# Expansion_board.net
KiCad netlist of a schematic drawn in Altium Designer
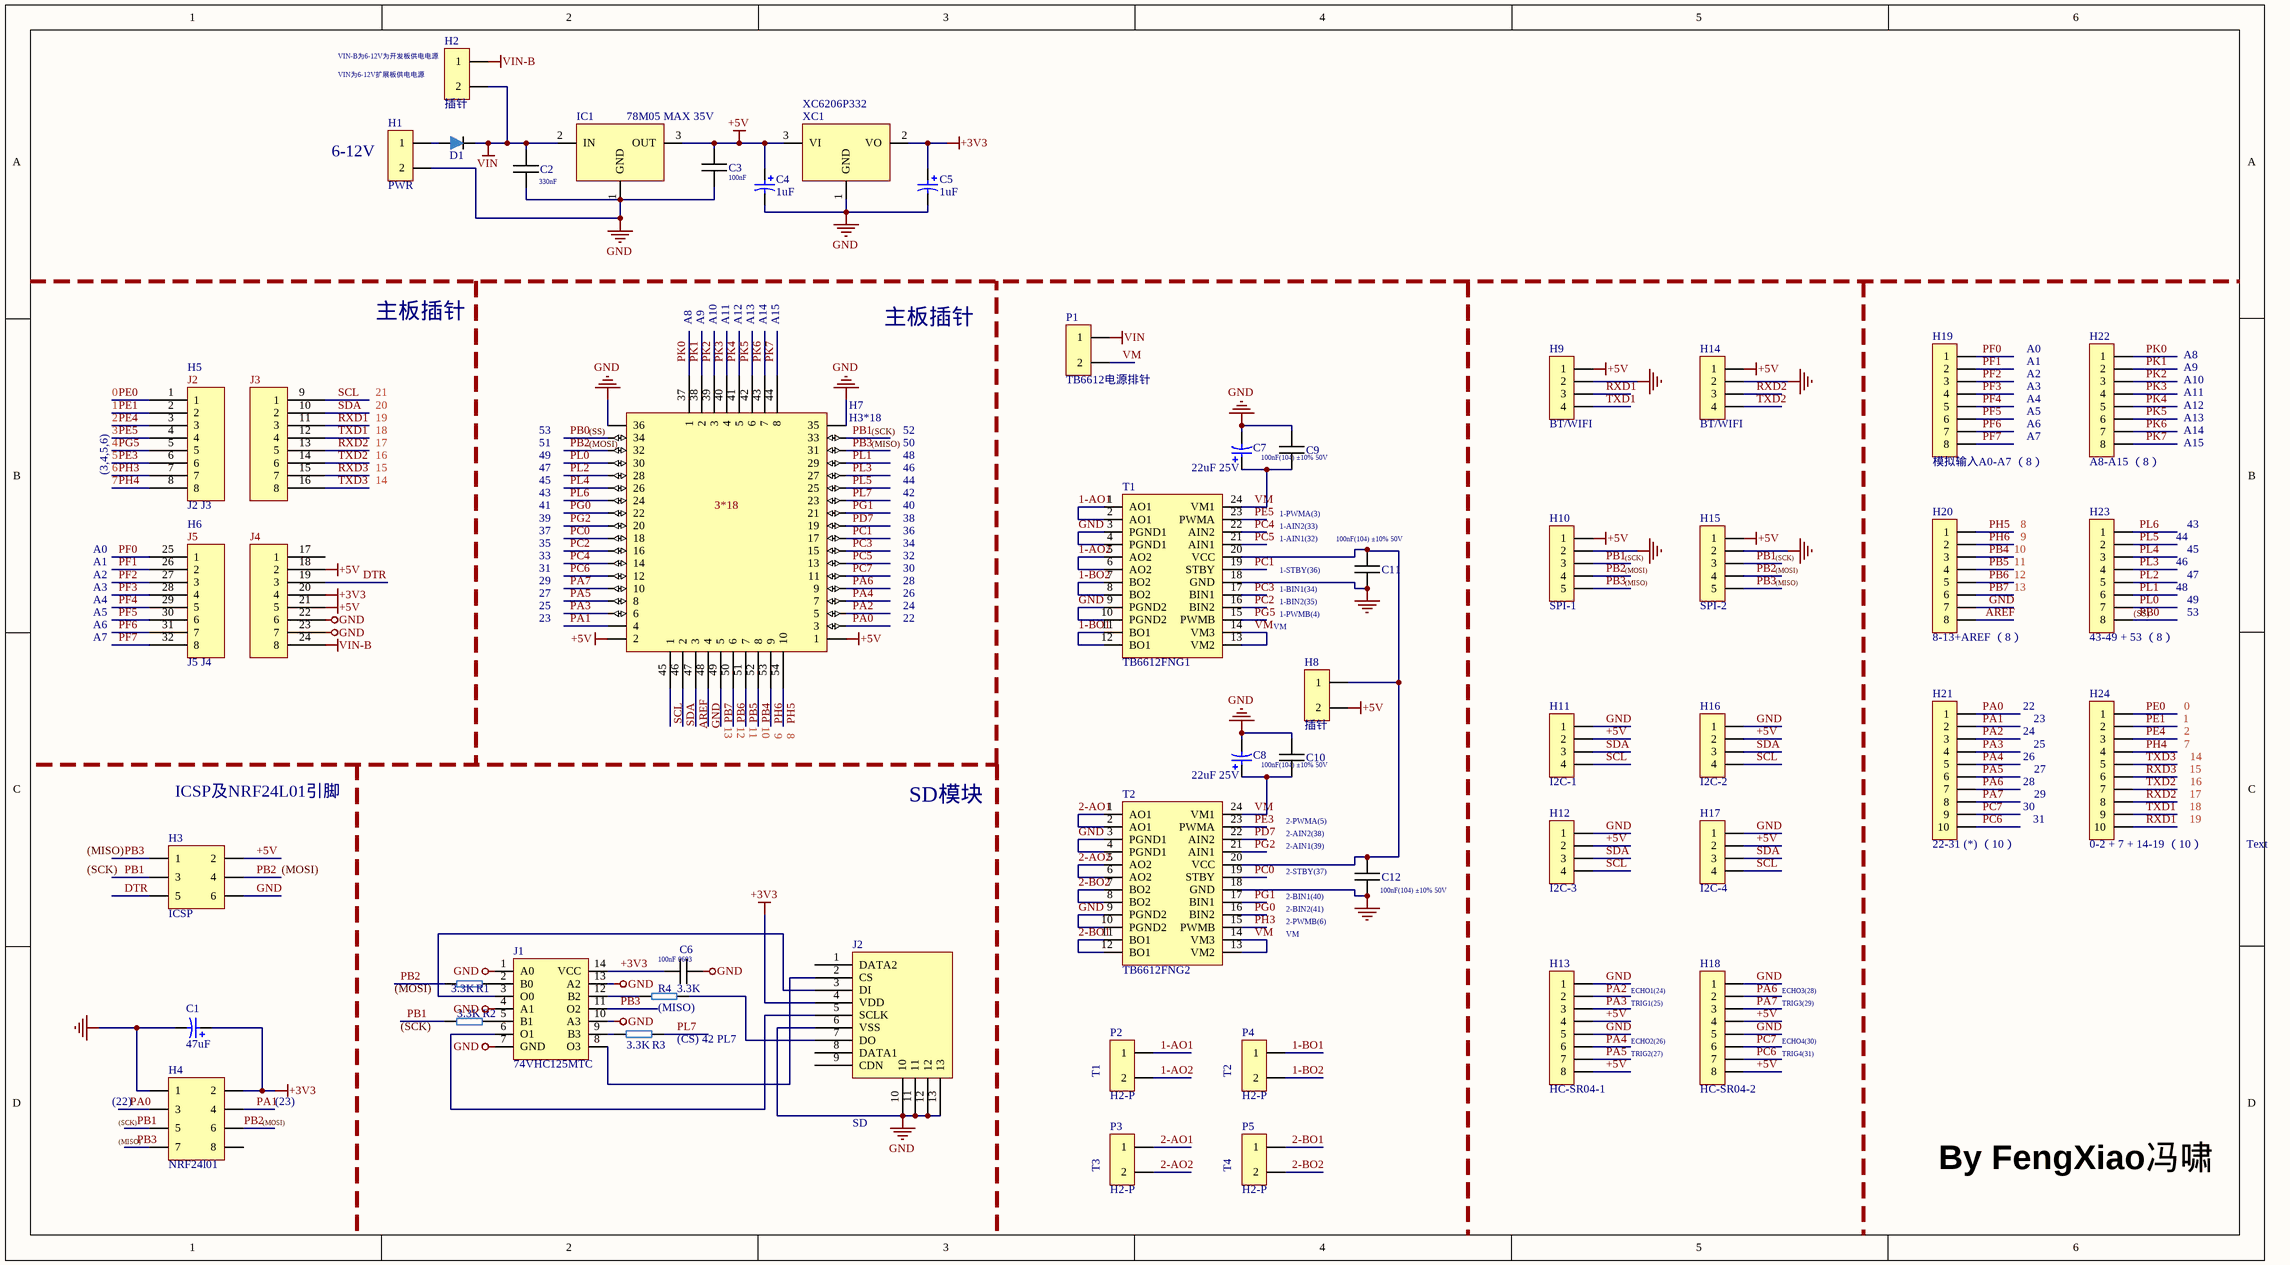
[diagram p0: Expansion board.SchDoc]

(export (version "E")
  (design (tool "Eeschema 10.0.6"))
  (components
    (comp (ref "C1")
      (value "47uF")
      (footprint "极性电容")
      (description "极性电容器")
      (fields (field (name "PUBLISHER") "Altium Limited"))
      (libsource (lib "Mega2560原理图库") (part "Cap Pol极性电容"))
    )
    (comp (ref "C2") (value "330nF") (footprint "0805") (libsource (lib "Expansion board") (part "CAP-N")))
    (comp (ref "C3") (value "100nF") (footprint "0805") (libsource (lib "Expansion board") (part "CAP-N")))
    (comp (ref "C4")
      (value "1uF")
      (footprint "0603")
      (description "极性电容器")
      (fields (field (name "PUBLISHER") "Altium Limited"))
      (libsource (lib "Expansion board") (part "Cap"))
    )
    (comp (ref "C5")
      (value "1uF")
      (footprint "0603")
      (description "极性电容器")
      (fields (field (name "PUBLISHER") "Altium Limited"))
      (libsource (lib "Expansion board") (part "Cap"))
    )
    (comp (ref "C6")
      (value "100nF 0603")
      (footprint "0603")
      (libsource (lib "Expansion board") (part "CAP-N"))
    )
    (comp (ref "C7")
      (value "22uF 25V")
      (footprint "极性电容")
      (description "极性电容器")
      (fields (field (name "PUBLISHER") "Altium Limited"))
      (libsource (lib "Mega2560原理图库") (part "Cap Pol极性电容"))
    )
    (comp (ref "C8")
      (value "22uF 25V")
      (footprint "极性电容")
      (description "极性电容器")
      (fields (field (name "PUBLISHER") "Altium Limited"))
      (libsource (lib "Mega2560原理图库") (part "Cap Pol极性电容"))
    )
    (comp (ref "C9")
      (value "100nF(104) ±10% 50V")
      (footprint "0805")
      (libsource (lib "Mega2560原理图库") (part "CAP-0805"))
    )
    (comp (ref "C10")
      (value "100nF(104) ±10% 50V")
      (footprint "0805")
      (libsource (lib "Mega2560原理图库") (part "CAP-0805"))
    )
    (comp (ref "C11")
      (value "100nF(104) ±10% 50V")
      (footprint "0805")
      (libsource (lib "Expansion board") (part "CAP-0805"))
    )
    (comp (ref "C12")
      (value "100nF(104) ±10% 50V")
      (footprint "0805")
      (libsource (lib "Mega2560原理图库") (part "CAP-0805"))
    )
    (comp (ref "D1") (value "二极管") (footprint "1206 +-") (libsource (lib "Expansion board") (part "二极管")))
    (comp (ref "H1") (value "PWR") (footprint "插线端子2P") (libsource (lib "Expansion board") (part "H2")))
    (comp (ref "H2")
      (value "插针")
      (footprint "H2")
      (description "排针类")
      (libsource (lib "Expansion board") (part "H2"))
    )
    (comp (ref "H3") (value "ICSP") (footprint "H2*3") (libsource (lib "Expansion board") (part "H3*2")))
    (comp (ref "H4")
      (value "NRF24l01")
      (footprint "H2*4")
      (libsource (lib "Expansion board") (part "Header 2*4"))
    )
    (comp (ref "H5") (value "J2 J3") (footprint "J2J3") (libsource (lib "Expansion board") (part "J2-3")))
    (comp (ref "H6") (value "J5 J4") (footprint "J5J4") (libsource (lib "Expansion board") (part "J5-4")))
    (comp (ref "H7") (value "H3*18") (footprint "H3*18") (libsource (lib "Expansion board") (part "H3*18")))
    (comp (ref "H8")
      (value "插针")
      (footprint "H2")
      (description "排针类")
      (libsource (lib "Expansion board") (part "H2"))
    )
    (comp (ref "H9") (value "BT/WIFI") (footprint "H4") (libsource (lib "Expansion board") (part "H4")))
    (comp (ref "H10") (value "SPI-1") (footprint "H5") (libsource (lib "Expansion board") (part "H5")))
    (comp (ref "H11") (value "I2C-1") (footprint "H4") (libsource (lib "Expansion board") (part "H4")))
    (comp (ref "H12") (value "I2C-3") (footprint "H4") (libsource (lib "Expansion board") (part "H4")))
    (comp (ref "H13") (value "HC-SR04-1") (footprint "H8") (libsource (lib "Expansion board") (part "H8")))
    (comp (ref "H14") (value "BT/WIFI") (footprint "H4") (libsource (lib "Expansion board") (part "H4")))
    (comp (ref "H15") (value "SPI-2") (footprint "H5") (libsource (lib "Expansion board") (part "H5")))
    (comp (ref "H16") (value "I2C-2") (footprint "H4") (libsource (lib "Expansion board") (part "H4")))
    (comp (ref "H17") (value "I2C-4") (footprint "H4") (libsource (lib "Expansion board") (part "H4")))
    (comp (ref "H18") (value "HC-SR04-2") (footprint "H8") (libsource (lib "Expansion board") (part "H8")))
    (comp (ref "H19")
      (value "模拟输入A0-A7 （8）")
      (footprint "H8")
      (libsource (lib "Expansion board") (part "H8"))
    )
    (comp (ref "H20")
      (value "8-13+AREF （8）")
      (footprint "H8")
      (libsource (lib "Expansion board") (part "H8"))
    )
    (comp (ref "H21")
      (value "22-31 (*) （10）")
      (footprint "H10")
      (libsource (lib "Expansion board") (part "H10"))
    )
    (comp (ref "H22") (value "A8-A15 （8）") (footprint "H8") (libsource (lib "Expansion board") (part "H8")))
    (comp (ref "H23")
      (value "43-49 + 53 （8）")
      (footprint "H8")
      (libsource (lib "Expansion board") (part "H8"))
    )
    (comp (ref "H24")
      (value "0-2 + 7 + 14-19 （10）")
      (footprint "H10")
      (libsource (lib "Expansion board") (part "H10"))
    )
    (comp (ref "IC1")
      (value "78M05 MAX 35V")
      (footprint "78M05")
      (description "MAX 18V")
      (libsource (lib "Expansion board") (part "78M05-5.0V"))
    )
    (comp (ref "J1")
      (value "74VHC125MTC")
      (footprint "74VHC125MTC")
      (libsource (lib "Expansion board") (part "74VHC125MCT"))
    )
    (comp (ref "J2") (value "SD") (footprint "SD") (libsource (lib "Expansion board") (part "SD")))
    (comp (ref "P1")
      (value "TB6612电源排针")
      (footprint "H2")
      (description "排管类")
      (libsource (lib "Expansion board") (part "H2-P"))
    )
    (comp (ref "P2")
      (value "H2-P")
      (footprint "插线端子2P")
      (description "排管类")
      (libsource (lib "Expansion board") (part "H2-P"))
    )
    (comp (ref "P3")
      (value "H2-P")
      (footprint "插线端子2P")
      (description "排管类")
      (libsource (lib "Expansion board") (part "H2-P"))
    )
    (comp (ref "P4")
      (value "H2-P")
      (footprint "插线端子2P")
      (description "排管类")
      (libsource (lib "Expansion board") (part "H2-P"))
    )
    (comp (ref "P5")
      (value "H2-P")
      (footprint "插线端子2P")
      (description "排管类")
      (libsource (lib "Expansion board") (part "H2-P"))
    )
    (comp (ref "R1") (value "3.3K") (footprint "0805") (libsource (lib "Expansion board") (part "RES")))
    (comp (ref "R2") (value "3.3K") (footprint "0805") (libsource (lib "Expansion board") (part "RES")))
    (comp (ref "R3") (value "3.3K") (footprint "0805") (libsource (lib "Expansion board") (part "RES")))
    (comp (ref "R4") (value "3.3K") (footprint "0805") (libsource (lib "Expansion board") (part "RES")))
    (comp (ref "T1")
      (value "TB6612FNG1")
      (footprint "TB6612GNG")
      (libsource (lib "Expansion board") (part "TB6612"))
    )
    (comp (ref "T2")
      (value "TB6612FNG2")
      (footprint "TB6612GNG")
      (libsource (lib "Expansion board") (part "TB6612"))
    )
    (comp (ref "XC1")
      (value "XC6206P332")
      (footprint "XC6206P332-3.3v")
      (description "3.3V限性稳压器")
      (libsource (lib "Expansion board") (part "XC6206P332"))
    )
  )
  (nets
    (net (code "1") (name "+3V3") (class "Default")
      (node (ref "C1") (pin "1") (pinfunction "1_1") (pintype "passive"))
      (node (ref "C5") (pin "1") (pinfunction "1_1") (pintype "passive"))
      (node (ref "C6") (pin "1") (pinfunction "1_1") (pintype "passive"))
      (node (ref "H4") (pin "2") (pinfunction "2_2") (pintype "passive"))
      (node (ref "H6") (pin "20") (pinfunction "4_20") (pintype "passive"))
      (node (ref "J1") (pin "14") (pinfunction "VCC_14") (pintype "passive"))
      (node (ref "J2") (pin "4") (pinfunction "VDD_4") (pintype "passive"))
      (node (ref "XC1") (pin "2") (pinfunction "VO_2") (pintype "passive"))
    )
    (net (code "2") (name "+5V") (class "Default")
      (node (ref "C3") (pin "2") (pinfunction "2_2") (pintype "passive"))
      (node (ref "C4") (pin "1") (pinfunction "1_1") (pintype "passive"))
      (node (ref "H10") (pin "1") (pinfunction "1_1") (pintype "passive"))
      (node (ref "H11") (pin "2") (pinfunction "2_2") (pintype "passive"))
      (node (ref "H12") (pin "2") (pinfunction "2_2") (pintype "passive"))
      (node (ref "H13") (pin "4") (pinfunction "4_4") (pintype "passive"))
      (node (ref "H13") (pin "8") (pinfunction "8_8") (pintype "passive"))
      (node (ref "H14") (pin "1") (pinfunction "1_1") (pintype "passive"))
      (node (ref "H15") (pin "1") (pinfunction "1_1") (pintype "passive"))
      (node (ref "H16") (pin "2") (pinfunction "2_2") (pintype "passive"))
      (node (ref "H17") (pin "2") (pinfunction "2_2") (pintype "passive"))
      (node (ref "H18") (pin "4") (pinfunction "4_4") (pintype "passive"))
      (node (ref "H18") (pin "8") (pinfunction "8_8") (pintype "passive"))
      (node (ref "H3") (pin "2") (pinfunction "2_2") (pintype "passive"))
      (node (ref "H6") (pin "18") (pinfunction "2_18") (pintype "passive"))
      (node (ref "H6") (pin "21") (pinfunction "5_21") (pintype "passive"))
      (node (ref "H7") (pin "1") (pinfunction "1_1") (pintype "power_in"))
      (node (ref "H7") (pin "2") (pinfunction "2_2") (pintype "power_in"))
      (node (ref "H8") (pin "2") (pinfunction "2_2") (pintype "passive"))
      (node (ref "H9") (pin "1") (pinfunction "1_1") (pintype "passive"))
      (node (ref "IC1") (pin "3") (pinfunction "OUT_3") (pintype "passive"))
      (node (ref "XC1") (pin "3") (pinfunction "VI_3") (pintype "passive"))
    )
    (net (code "3") (name "/1-AO1") (class "Default")
      (node (ref "P2") (pin "1") (pinfunction "1_1") (pintype "passive"))
      (node (ref "T1") (pin "1") (pinfunction "AO1_1") (pintype "passive"))
      (node (ref "T1") (pin "2") (pinfunction "AO1_2") (pintype "passive"))
    )
    (net (code "4") (name "/1-AO2") (class "Default")
      (node (ref "P2") (pin "2") (pinfunction "2_2") (pintype "passive"))
      (node (ref "T1") (pin "5") (pinfunction "AO2_5") (pintype "passive"))
      (node (ref "T1") (pin "6") (pinfunction "AO2_6") (pintype "passive"))
    )
    (net (code "5") (name "/1-BO1") (class "Default")
      (node (ref "P4") (pin "1") (pinfunction "1_1") (pintype "passive"))
      (node (ref "T1") (pin "11") (pinfunction "BO1_11") (pintype "passive"))
      (node (ref "T1") (pin "12") (pinfunction "BO1_12") (pintype "passive"))
    )
    (net (code "6") (name "/1-BO2") (class "Default")
      (node (ref "P4") (pin "2") (pinfunction "2_2") (pintype "passive"))
      (node (ref "T1") (pin "7") (pinfunction "BO2_7") (pintype "passive"))
      (node (ref "T1") (pin "8") (pinfunction "BO2_8") (pintype "passive"))
    )
    (net (code "7") (name "/2-AO1") (class "Default")
      (node (ref "P3") (pin "1") (pinfunction "1_1") (pintype "passive"))
      (node (ref "T2") (pin "1") (pinfunction "AO1_1") (pintype "passive"))
      (node (ref "T2") (pin "2") (pinfunction "AO1_2") (pintype "passive"))
    )
    (net (code "8") (name "/2-AO2") (class "Default")
      (node (ref "P3") (pin "2") (pinfunction "2_2") (pintype "passive"))
      (node (ref "T2") (pin "5") (pinfunction "AO2_5") (pintype "passive"))
      (node (ref "T2") (pin "6") (pinfunction "AO2_6") (pintype "passive"))
    )
    (net (code "9") (name "/2-BO1") (class "Default")
      (node (ref "P5") (pin "1") (pinfunction "1_1") (pintype "passive"))
      (node (ref "T2") (pin "11") (pinfunction "BO1_11") (pintype "passive"))
      (node (ref "T2") (pin "12") (pinfunction "BO1_12") (pintype "passive"))
    )
    (net (code "10") (name "/2-BO2") (class "Default")
      (node (ref "P5") (pin "2") (pinfunction "2_2") (pintype "passive"))
      (node (ref "T2") (pin "7") (pinfunction "BO2_7") (pintype "passive"))
      (node (ref "T2") (pin "8") (pinfunction "BO2_8") (pintype "passive"))
    )
    (net (code "11") (name "/AREF") (class "Default")
      (node (ref "H20") (pin "8") (pinfunction "8_8") (pintype "passive"))
      (node (ref "H7") (pin "47") (pinfunction "3_47") (pintype "passive"))
    )
    (net (code "12") (name "/DTR") (class "Default")
      (node (ref "H3") (pin "5") (pinfunction "5_5") (pintype "passive"))
      (node (ref "H6") (pin "19") (pinfunction "3_19") (pintype "passive"))
    )
    (net (code "13") (name "/PA0") (class "Default")
      (node (ref "H21") (pin "1") (pinfunction "1_1") (pintype "passive"))
      (node (ref "H4") (pin "3") (pinfunction "3_3") (pintype "passive"))
      (node (ref "H7") (pin "3") (pinfunction "3_3") (pintype "bidirectional"))
    )
    (net (code "14") (name "/PA1") (class "Default")
      (node (ref "H21") (pin "2") (pinfunction "2_2") (pintype "passive"))
      (node (ref "H4") (pin "4") (pinfunction "4_4") (pintype "passive"))
      (node (ref "H7") (pin "4") (pinfunction "4_4") (pintype "passive"))
    )
    (net (code "15") (name "/PA2") (class "Default")
      (node (ref "H13") (pin "2") (pinfunction "2_2") (pintype "passive"))
      (node (ref "H21") (pin "3") (pinfunction "3_3") (pintype "passive"))
      (node (ref "H7") (pin "5") (pinfunction "5_5") (pintype "bidirectional"))
    )
    (net (code "16") (name "/PA3") (class "Default")
      (node (ref "H13") (pin "3") (pinfunction "3_3") (pintype "passive"))
      (node (ref "H21") (pin "4") (pinfunction "4_4") (pintype "passive"))
      (node (ref "H7") (pin "6") (pinfunction "6_6") (pintype "bidirectional"))
    )
    (net (code "17") (name "/PA4") (class "Default")
      (node (ref "H13") (pin "6") (pinfunction "6_6") (pintype "passive"))
      (node (ref "H21") (pin "5") (pinfunction "5_5") (pintype "passive"))
      (node (ref "H7") (pin "7") (pinfunction "7_7") (pintype "bidirectional"))
    )
    (net (code "18") (name "/PA5") (class "Default")
      (node (ref "H13") (pin "7") (pinfunction "7_7") (pintype "passive"))
      (node (ref "H21") (pin "6") (pinfunction "6_6") (pintype "passive"))
      (node (ref "H7") (pin "8") (pinfunction "8_8") (pintype "bidirectional"))
    )
    (net (code "19") (name "/PA6") (class "Default")
      (node (ref "H18") (pin "2") (pinfunction "2_2") (pintype "passive"))
      (node (ref "H21") (pin "7") (pinfunction "7_7") (pintype "passive"))
      (node (ref "H7") (pin "9") (pinfunction "9_9") (pintype "bidirectional"))
    )
    (net (code "20") (name "/PA7") (class "Default")
      (node (ref "H18") (pin "3") (pinfunction "3_3") (pintype "passive"))
      (node (ref "H21") (pin "8") (pinfunction "8_8") (pintype "passive"))
      (node (ref "H7") (pin "10") (pinfunction "10_10") (pintype "bidirectional"))
    )
    (net (code "21") (name "/PB0") (class "Default")
      (node (ref "H23") (pin "8") (pinfunction "8_8") (pintype "passive"))
      (node (ref "H7") (pin "34") (pinfunction "34_34") (pintype "bidirectional"))
    )
    (net (code "22") (name "/PB1") (class "Default")
      (node (ref "H10") (pin "3") (pinfunction "3_3") (pintype "passive"))
      (node (ref "H15") (pin "3") (pinfunction "3_3") (pintype "passive"))
      (node (ref "H3") (pin "3") (pinfunction "3_3") (pintype "passive"))
      (node (ref "H4") (pin "5") (pinfunction "5_5") (pintype "passive"))
      (node (ref "H7") (pin "33") (pinfunction "33_33") (pintype "bidirectional"))
      (node (ref "R2") (pin "1") (pinfunction "1_1") (pintype "passive"))
    )
    (net (code "23") (name "/PB2") (class "Default")
      (node (ref "H10") (pin "4") (pinfunction "4_4") (pintype "passive"))
      (node (ref "H15") (pin "4") (pinfunction "4_4") (pintype "passive"))
      (node (ref "H3") (pin "4") (pinfunction "4_4") (pintype "passive"))
      (node (ref "H4") (pin "6") (pinfunction "6_6") (pintype "passive"))
      (node (ref "H7") (pin "32") (pinfunction "32_32") (pintype "bidirectional"))
      (node (ref "R1") (pin "1") (pinfunction "1_1") (pintype "passive"))
    )
    (net (code "24") (name "/PB3") (class "Default")
      (node (ref "H10") (pin "5") (pinfunction "5_5") (pintype "passive"))
      (node (ref "H15") (pin "5") (pinfunction "5_5") (pintype "passive"))
      (node (ref "H3") (pin "1") (pinfunction "1_1") (pintype "passive"))
      (node (ref "H4") (pin "7") (pinfunction "7_7") (pintype "passive"))
      (node (ref "H7") (pin "31") (pinfunction "31_31") (pintype "bidirectional"))
      (node (ref "J1") (pin "11") (pinfunction "O2_11") (pintype "passive"))
    )
    (net (code "25") (name "/PB4") (class "Default")
      (node (ref "H20") (pin "3") (pinfunction "3_3") (pintype "passive"))
      (node (ref "H7") (pin "52") (pinfunction "8_52") (pintype "passive"))
    )
    (net (code "26") (name "/PB5") (class "Default")
      (node (ref "H20") (pin "4") (pinfunction "4_4") (pintype "passive"))
      (node (ref "H7") (pin "51") (pinfunction "7_51") (pintype "passive"))
    )
    (net (code "27") (name "/PB6") (class "Default")
      (node (ref "H20") (pin "5") (pinfunction "5_5") (pintype "passive"))
      (node (ref "H7") (pin "50") (pinfunction "6_50") (pintype "passive"))
    )
    (net (code "28") (name "/PB7") (class "Default")
      (node (ref "H20") (pin "6") (pinfunction "6_6") (pintype "passive"))
      (node (ref "H7") (pin "49") (pinfunction "5_49") (pintype "passive"))
    )
    (net (code "29") (name "/PC0") (class "Default")
      (node (ref "H7") (pin "18") (pinfunction "18_18") (pintype "bidirectional"))
      (node (ref "T2") (pin "19") (pinfunction "STBY_19") (pintype "passive"))
    )
    (net (code "30") (name "/PC1") (class "Default")
      (node (ref "H7") (pin "17") (pinfunction "17_17") (pintype "bidirectional"))
      (node (ref "T1") (pin "19") (pinfunction "STBY_19") (pintype "passive"))
    )
    (net (code "31") (name "/PC2") (class "Default")
      (node (ref "H7") (pin "16") (pinfunction "16_16") (pintype "bidirectional"))
      (node (ref "T1") (pin "16") (pinfunction "BIN2_16") (pintype "passive"))
    )
    (net (code "32") (name "/PC3") (class "Default")
      (node (ref "H7") (pin "15") (pinfunction "15_15") (pintype "bidirectional"))
      (node (ref "T1") (pin "17") (pinfunction "BIN1_17") (pintype "passive"))
    )
    (net (code "33") (name "/PC4") (class "Default")
      (node (ref "H7") (pin "14") (pinfunction "14_14") (pintype "bidirectional"))
      (node (ref "T1") (pin "22") (pinfunction "AIN2_22") (pintype "passive"))
    )
    (net (code "34") (name "/PC5") (class "Default")
      (node (ref "H7") (pin "13") (pinfunction "13_13") (pintype "bidirectional"))
      (node (ref "T1") (pin "21") (pinfunction "AIN1_21") (pintype "passive"))
    )
    (net (code "35") (name "/PC6") (class "Default")
      (node (ref "H18") (pin "7") (pinfunction "7_7") (pintype "passive"))
      (node (ref "H21") (pin "10") (pinfunction "10_10") (pintype "passive"))
      (node (ref "H7") (pin "12") (pinfunction "12_12") (pintype "bidirectional"))
    )
    (net (code "36") (name "/PC7") (class "Default")
      (node (ref "H18") (pin "6") (pinfunction "6_6") (pintype "passive"))
      (node (ref "H21") (pin "9") (pinfunction "9_9") (pintype "passive"))
      (node (ref "H7") (pin "11") (pinfunction "11_11") (pintype "bidirectional"))
    )
    (net (code "37") (name "/PD7") (class "Default")
      (node (ref "H7") (pin "19") (pinfunction "19_19") (pintype "bidirectional"))
      (node (ref "T2") (pin "22") (pinfunction "AIN2_22") (pintype "passive"))
    )
    (net (code "38") (name "/PE0") (class "Default")
      (node (ref "H24") (pin "1") (pinfunction "1_1") (pintype "passive"))
      (node (ref "H5") (pin "1") (pinfunction "1_1") (pintype "passive"))
    )
    (net (code "39") (name "/PE1") (class "Default")
      (node (ref "H24") (pin "2") (pinfunction "2_2") (pintype "passive"))
      (node (ref "H5") (pin "2") (pinfunction "2_2") (pintype "passive"))
    )
    (net (code "40") (name "/PE3") (class "Default")
      (node (ref "H5") (pin "6") (pinfunction "6_6") (pintype "passive"))
      (node (ref "T2") (pin "23") (pinfunction "PWMA_23") (pintype "passive"))
    )
    (net (code "41") (name "/PE4") (class "Default")
      (node (ref "H24") (pin "3") (pinfunction "3_3") (pintype "passive"))
      (node (ref "H5") (pin "3") (pinfunction "3_3") (pintype "passive"))
    )
    (net (code "42") (name "/PE5") (class "Default")
      (node (ref "H5") (pin "4") (pinfunction "4_4") (pintype "passive"))
      (node (ref "T1") (pin "23") (pinfunction "PWMA_23") (pintype "passive"))
    )
    (net (code "43") (name "/PF0") (class "Default")
      (node (ref "H19") (pin "1") (pinfunction "1_1") (pintype "passive"))
      (node (ref "H6") (pin "25") (pinfunction "1_25") (pintype "passive"))
    )
    (net (code "44") (name "/PF1") (class "Default")
      (node (ref "H19") (pin "2") (pinfunction "2_2") (pintype "passive"))
      (node (ref "H6") (pin "26") (pinfunction "2_26") (pintype "passive"))
    )
    (net (code "45") (name "/PF2") (class "Default")
      (node (ref "H19") (pin "3") (pinfunction "3_3") (pintype "passive"))
      (node (ref "H6") (pin "27") (pinfunction "3_27") (pintype "passive"))
    )
    (net (code "46") (name "/PF3") (class "Default")
      (node (ref "H19") (pin "4") (pinfunction "4_4") (pintype "passive"))
      (node (ref "H6") (pin "28") (pinfunction "4_28") (pintype "passive"))
    )
    (net (code "47") (name "/PF4") (class "Default")
      (node (ref "H19") (pin "5") (pinfunction "5_5") (pintype "passive"))
      (node (ref "H6") (pin "29") (pinfunction "5_29") (pintype "passive"))
    )
    (net (code "48") (name "/PF5") (class "Default")
      (node (ref "H19") (pin "6") (pinfunction "6_6") (pintype "passive"))
      (node (ref "H6") (pin "30") (pinfunction "6_30") (pintype "passive"))
    )
    (net (code "49") (name "/PF6") (class "Default")
      (node (ref "H19") (pin "7") (pinfunction "7_7") (pintype "passive"))
      (node (ref "H6") (pin "31") (pinfunction "7_31") (pintype "passive"))
    )
    (net (code "50") (name "/PF7") (class "Default")
      (node (ref "H19") (pin "8") (pinfunction "8_8") (pintype "passive"))
      (node (ref "H6") (pin "32") (pinfunction "8_32") (pintype "passive"))
    )
    (net (code "51") (name "/PG0") (class "Default")
      (node (ref "H7") (pin "22") (pinfunction "22_22") (pintype "bidirectional"))
      (node (ref "T2") (pin "16") (pinfunction "BIN2_16") (pintype "passive"))
    )
    (net (code "52") (name "/PG1") (class "Default")
      (node (ref "H7") (pin "21") (pinfunction "21_21") (pintype "bidirectional"))
      (node (ref "T2") (pin "17") (pinfunction "BIN1_17") (pintype "passive"))
    )
    (net (code "53") (name "/PG2") (class "Default")
      (node (ref "H7") (pin "20") (pinfunction "20_20") (pintype "bidirectional"))
      (node (ref "T2") (pin "21") (pinfunction "AIN1_21") (pintype "passive"))
    )
    (net (code "54") (name "/PG5") (class "Default")
      (node (ref "H5") (pin "5") (pinfunction "5_5") (pintype "passive"))
      (node (ref "T1") (pin "15") (pinfunction "PWMB_15") (pintype "passive"))
    )
    (net (code "55") (name "/PH3") (class "Default")
      (node (ref "H5") (pin "7") (pinfunction "7_7") (pintype "passive"))
      (node (ref "T2") (pin "15") (pinfunction "PWMB_15") (pintype "passive"))
    )
    (net (code "56") (name "/PH4") (class "Default")
      (node (ref "H24") (pin "4") (pinfunction "4_4") (pintype "passive"))
      (node (ref "H5") (pin "8") (pinfunction "8_8") (pintype "passive"))
    )
    (net (code "57") (name "/PH5") (class "Default")
      (node (ref "H20") (pin "1") (pinfunction "1_1") (pintype "passive"))
      (node (ref "H7") (pin "54") (pinfunction "10_54") (pintype "passive"))
    )
    (net (code "58") (name "/PH6") (class "Default")
      (node (ref "H20") (pin "2") (pinfunction "2_2") (pintype "passive"))
      (node (ref "H7") (pin "53") (pinfunction "9_53") (pintype "passive"))
    )
    (net (code "59") (name "/PK0") (class "Default")
      (node (ref "H22") (pin "1") (pinfunction "1_1") (pintype "passive"))
      (node (ref "H7") (pin "37") (pinfunction "1_37") (pintype "passive"))
    )
    (net (code "60") (name "/PK1") (class "Default")
      (node (ref "H22") (pin "2") (pinfunction "2_2") (pintype "passive"))
      (node (ref "H7") (pin "38") (pinfunction "2_38") (pintype "passive"))
    )
    (net (code "61") (name "/PK2") (class "Default")
      (node (ref "H22") (pin "3") (pinfunction "3_3") (pintype "passive"))
      (node (ref "H7") (pin "39") (pinfunction "3_39") (pintype "passive"))
    )
    (net (code "62") (name "/PK3") (class "Default")
      (node (ref "H22") (pin "4") (pinfunction "4_4") (pintype "passive"))
      (node (ref "H7") (pin "40") (pinfunction "4_40") (pintype "passive"))
    )
    (net (code "63") (name "/PK4") (class "Default")
      (node (ref "H22") (pin "5") (pinfunction "5_5") (pintype "passive"))
      (node (ref "H7") (pin "41") (pinfunction "5_41") (pintype "passive"))
    )
    (net (code "64") (name "/PK5") (class "Default")
      (node (ref "H22") (pin "6") (pinfunction "6_6") (pintype "passive"))
      (node (ref "H7") (pin "42") (pinfunction "6_42") (pintype "passive"))
    )
    (net (code "65") (name "/PK6") (class "Default")
      (node (ref "H22") (pin "7") (pinfunction "7_7") (pintype "passive"))
      (node (ref "H7") (pin "43") (pinfunction "7_43") (pintype "passive"))
    )
    (net (code "66") (name "/PK7") (class "Default")
      (node (ref "H22") (pin "8") (pinfunction "8_8") (pintype "passive"))
      (node (ref "H7") (pin "44") (pinfunction "8_44") (pintype "passive"))
    )
    (net (code "67") (name "/PL0") (class "Default")
      (node (ref "H23") (pin "7") (pinfunction "7_7") (pintype "passive"))
      (node (ref "H7") (pin "30") (pinfunction "30_30") (pintype "bidirectional"))
    )
    (net (code "68") (name "/PL1") (class "Default")
      (node (ref "H23") (pin "6") (pinfunction "6_6") (pintype "passive"))
      (node (ref "H7") (pin "29") (pinfunction "29_29") (pintype "bidirectional"))
    )
    (net (code "69") (name "/PL2") (class "Default")
      (node (ref "H23") (pin "5") (pinfunction "5_5") (pintype "passive"))
      (node (ref "H7") (pin "28") (pinfunction "28_28") (pintype "bidirectional"))
    )
    (net (code "70") (name "/PL3") (class "Default")
      (node (ref "H23") (pin "4") (pinfunction "4_4") (pintype "passive"))
      (node (ref "H7") (pin "27") (pinfunction "27_27") (pintype "bidirectional"))
    )
    (net (code "71") (name "/PL4") (class "Default")
      (node (ref "H23") (pin "3") (pinfunction "3_3") (pintype "passive"))
      (node (ref "H7") (pin "26") (pinfunction "26_26") (pintype "bidirectional"))
    )
    (net (code "72") (name "/PL5") (class "Default")
      (node (ref "H23") (pin "2") (pinfunction "2_2") (pintype "passive"))
      (node (ref "H7") (pin "25") (pinfunction "25_25") (pintype "bidirectional"))
    )
    (net (code "73") (name "/PL6") (class "Default")
      (node (ref "H23") (pin "1") (pinfunction "1_1") (pintype "passive"))
      (node (ref "H7") (pin "24") (pinfunction "24_24") (pintype "bidirectional"))
    )
    (net (code "74") (name "/PL7") (class "Default")
      (node (ref "H7") (pin "23") (pinfunction "23_23") (pintype "bidirectional"))
      (node (ref "R3") (pin "2") (pinfunction "2_2") (pintype "passive"))
    )
    (net (code "75") (name "/RXD1") (class "Default")
      (node (ref "H24") (pin "10") (pinfunction "10_10") (pintype "passive"))
      (node (ref "H5") (pin "11") (pinfunction "3_11") (pintype "passive"))
      (node (ref "H9") (pin "3") (pinfunction "3_3") (pintype "passive"))
    )
    (net (code "76") (name "/RXD2") (class "Default")
      (node (ref "H14") (pin "3") (pinfunction "3_3") (pintype "passive"))
      (node (ref "H24") (pin "8") (pinfunction "8_8") (pintype "passive"))
      (node (ref "H5") (pin "13") (pinfunction "5_13") (pintype "passive"))
    )
    (net (code "77") (name "/RXD3") (class "Default")
      (node (ref "H24") (pin "6") (pinfunction "6_6") (pintype "passive"))
      (node (ref "H5") (pin "15") (pinfunction "7_15") (pintype "passive"))
    )
    (net (code "78") (name "/SCL") (class "Default")
      (node (ref "H11") (pin "4") (pinfunction "4_4") (pintype "passive"))
      (node (ref "H12") (pin "4") (pinfunction "4_4") (pintype "passive"))
      (node (ref "H16") (pin "4") (pinfunction "4_4") (pintype "passive"))
      (node (ref "H17") (pin "4") (pinfunction "4_4") (pintype "passive"))
      (node (ref "H5") (pin "9") (pinfunction "1_9") (pintype "passive"))
      (node (ref "H7") (pin "45") (pinfunction "1_45") (pintype "passive"))
    )
    (net (code "79") (name "/SDA") (class "Default")
      (node (ref "H11") (pin "3") (pinfunction "3_3") (pintype "passive"))
      (node (ref "H12") (pin "3") (pinfunction "3_3") (pintype "passive"))
      (node (ref "H16") (pin "3") (pinfunction "3_3") (pintype "passive"))
      (node (ref "H17") (pin "3") (pinfunction "3_3") (pintype "passive"))
      (node (ref "H5") (pin "10") (pinfunction "2_10") (pintype "passive"))
      (node (ref "H7") (pin "46") (pinfunction "2_46") (pintype "passive"))
    )
    (net (code "80") (name "/TXD1") (class "Default")
      (node (ref "H24") (pin "9") (pinfunction "9_9") (pintype "passive"))
      (node (ref "H5") (pin "12") (pinfunction "4_12") (pintype "passive"))
      (node (ref "H9") (pin "4") (pinfunction "4_4") (pintype "passive"))
    )
    (net (code "81") (name "/TXD2") (class "Default")
      (node (ref "H14") (pin "4") (pinfunction "4_4") (pintype "passive"))
      (node (ref "H24") (pin "7") (pinfunction "7_7") (pintype "passive"))
      (node (ref "H5") (pin "14") (pinfunction "6_14") (pintype "passive"))
    )
    (net (code "82") (name "/TXD3") (class "Default")
      (node (ref "H24") (pin "5") (pinfunction "5_5") (pintype "passive"))
      (node (ref "H5") (pin "16") (pinfunction "8_16") (pintype "passive"))
    )
    (net (code "83") (name "/VM") (class "Default")
      (node (ref "C10") (pin "1") (pinfunction "1_1") (pintype "passive"))
      (node (ref "C7") (pin "1") (pinfunction "1_1") (pintype "passive"))
      (node (ref "C8") (pin "1") (pinfunction "1_1") (pintype "passive"))
      (node (ref "C9") (pin "1") (pinfunction "1_1") (pintype "passive"))
      (node (ref "P1") (pin "2") (pinfunction "2_2") (pintype "passive"))
      (node (ref "T1") (pin "13") (pinfunction "VM2_13") (pintype "passive"))
      (node (ref "T1") (pin "14") (pinfunction "VM3_14") (pintype "passive"))
      (node (ref "T1") (pin "24") (pinfunction "VM1_24") (pintype "passive"))
      (node (ref "T2") (pin "13") (pinfunction "VM2_13") (pintype "passive"))
      (node (ref "T2") (pin "14") (pinfunction "VM3_14") (pintype "passive"))
      (node (ref "T2") (pin "24") (pinfunction "VM1_24") (pintype "passive"))
    )
    (net (code "84") (name "GND") (class "Default")
      (node (ref "C1") (pin "2") (pinfunction "2_2") (pintype "passive"))
      (node (ref "C10") (pin "2") (pinfunction "2_2") (pintype "passive"))
      (node (ref "C11") (pin "1") (pinfunction "1_1") (pintype "passive"))
      (node (ref "C12") (pin "1") (pinfunction "1_1") (pintype "passive"))
      (node (ref "C2") (pin "1") (pinfunction "1_1") (pintype "passive"))
      (node (ref "C3") (pin "1") (pinfunction "1_1") (pintype "passive"))
      (node (ref "C4") (pin "2") (pinfunction "2_2") (pintype "passive"))
      (node (ref "C5") (pin "2") (pinfunction "2_2") (pintype "passive"))
      (node (ref "C6") (pin "2") (pinfunction "2_2") (pintype "passive"))
      (node (ref "C7") (pin "2") (pinfunction "2_2") (pintype "passive"))
      (node (ref "C8") (pin "2") (pinfunction "2_2") (pintype "passive"))
      (node (ref "C9") (pin "2") (pinfunction "2_2") (pintype "passive"))
      (node (ref "H1") (pin "2") (pinfunction "2_2") (pintype "passive"))
      (node (ref "H10") (pin "2") (pinfunction "2_2") (pintype "passive"))
      (node (ref "H11") (pin "1") (pinfunction "1_1") (pintype "passive"))
      (node (ref "H12") (pin "1") (pinfunction "1_1") (pintype "passive"))
      (node (ref "H13") (pin "1") (pinfunction "1_1") (pintype "passive"))
      (node (ref "H13") (pin "5") (pinfunction "5_5") (pintype "passive"))
      (node (ref "H14") (pin "2") (pinfunction "2_2") (pintype "passive"))
      (node (ref "H15") (pin "2") (pinfunction "2_2") (pintype "passive"))
      (node (ref "H16") (pin "1") (pinfunction "1_1") (pintype "passive"))
      (node (ref "H17") (pin "1") (pinfunction "1_1") (pintype "passive"))
      (node (ref "H18") (pin "1") (pinfunction "1_1") (pintype "passive"))
      (node (ref "H18") (pin "5") (pinfunction "5_5") (pintype "passive"))
      (node (ref "H20") (pin "7") (pinfunction "7_7") (pintype "passive"))
      (node (ref "H3") (pin "6") (pinfunction "6_6") (pintype "passive"))
      (node (ref "H4") (pin "1") (pinfunction "1_1") (pintype "passive"))
      (node (ref "H6") (pin "22") (pinfunction "6_22") (pintype "passive"))
      (node (ref "H6") (pin "23") (pinfunction "7_23") (pintype "passive"))
      (node (ref "H7") (pin "35") (pinfunction "35_35") (pintype "power_in"))
      (node (ref "H7") (pin "36") (pinfunction "36_36") (pintype "power_in"))
      (node (ref "H7") (pin "48") (pinfunction "4_48") (pintype "passive"))
      (node (ref "H9") (pin "2") (pinfunction "2_2") (pintype "passive"))
      (node (ref "IC1") (pin "1") (pinfunction "GND_1") (pintype "passive"))
      (node (ref "J1") (pin "1") (pinfunction "A0_1") (pintype "passive"))
      (node (ref "J1") (pin "10") (pinfunction "A3_10") (pintype "passive"))
      (node (ref "J1") (pin "13") (pinfunction "A2_13") (pintype "passive"))
      (node (ref "J1") (pin "4") (pinfunction "A1_4") (pintype "passive"))
      (node (ref "J1") (pin "7") (pinfunction "GND_7") (pintype "passive"))
      (node (ref "J2") (pin "10") (pinfunction "10_10") (pintype "passive"))
      (node (ref "J2") (pin "11") (pinfunction "11_11") (pintype "passive"))
      (node (ref "J2") (pin "12") (pinfunction "12_12") (pintype "passive"))
      (node (ref "J2") (pin "13") (pinfunction "13_13") (pintype "passive"))
      (node (ref "J2") (pin "6") (pinfunction "VSS_6") (pintype "passive"))
      (node (ref "T1") (pin "10") (pinfunction "PGND2_10") (pintype "passive"))
      (node (ref "T1") (pin "18") (pinfunction "GND_18") (pintype "passive"))
      (node (ref "T1") (pin "3") (pinfunction "PGND1_3") (pintype "passive"))
      (node (ref "T1") (pin "4") (pinfunction "PGND1_4") (pintype "passive"))
      (node (ref "T1") (pin "9") (pinfunction "PGND2_9") (pintype "passive"))
      (node (ref "T2") (pin "10") (pinfunction "PGND2_10") (pintype "passive"))
      (node (ref "T2") (pin "18") (pinfunction "GND_18") (pintype "passive"))
      (node (ref "T2") (pin "3") (pinfunction "PGND1_3") (pintype "passive"))
      (node (ref "T2") (pin "4") (pinfunction "PGND1_4") (pintype "passive"))
      (node (ref "T2") (pin "9") (pinfunction "PGND2_9") (pintype "passive"))
      (node (ref "XC1") (pin "1") (pinfunction "GND_1") (pintype "passive"))
    )
    (net (code "85") (name "Net-(D1-Pad1)") (class "Default")
      (node (ref "D1") (pin "1") (pinfunction "1_1") (pintype "passive"))
      (node (ref "H1") (pin "1") (pinfunction "1_1") (pintype "passive"))
    )
    (net (code "86") (name "Net-(J1-B0)") (class "Default")
      (node (ref "J1") (pin "2") (pinfunction "B0_2") (pintype "passive"))
      (node (ref "R1") (pin "2") (pinfunction "2_2") (pintype "passive"))
    )
    (net (code "87") (name "Net-(J1-B1)") (class "Default")
      (node (ref "J1") (pin "5") (pinfunction "B1_5") (pintype "passive"))
      (node (ref "R2") (pin "2") (pinfunction "2_2") (pintype "passive"))
    )
    (net (code "88") (name "Net-(J1-B2)") (class "Default")
      (node (ref "J1") (pin "12") (pinfunction "B2_12") (pintype "passive"))
      (node (ref "R4") (pin "1") (pinfunction "1_1") (pintype "passive"))
    )
    (net (code "89") (name "Net-(J1-B3)") (class "Default")
      (node (ref "J1") (pin "9") (pinfunction "B3_9") (pintype "passive"))
      (node (ref "R3") (pin "1") (pinfunction "1_1") (pintype "passive"))
    )
    (net (code "90") (name "Net-(J1-O0)") (class "Default")
      (node (ref "J1") (pin "3") (pinfunction "O0_3") (pintype "passive"))
      (node (ref "J2") (pin "3") (pinfunction "DI_3") (pintype "passive"))
    )
    (net (code "91") (name "Net-(J1-O1)") (class "Default")
      (node (ref "J1") (pin "6") (pinfunction "O1_6") (pintype "passive"))
      (node (ref "J2") (pin "5") (pinfunction "SCLK_5") (pintype "passive"))
    )
    (net (code "92") (name "Net-(J1-O3)") (class "Default")
      (node (ref "J1") (pin "8") (pinfunction "O3_8") (pintype "passive"))
      (node (ref "J2") (pin "2") (pinfunction "CS_2") (pintype "passive"))
    )
    (net (code "93") (name "Net-(J2-DO)") (class "Default")
      (node (ref "J2") (pin "7") (pinfunction "DO_7") (pintype "passive"))
      (node (ref "R4") (pin "2") (pinfunction "2_2") (pintype "passive"))
    )
    (net (code "94") (name "Net-(T1-VCC)") (class "Default")
      (node (ref "C11") (pin "2") (pinfunction "2_2") (pintype "passive"))
      (node (ref "C12") (pin "2") (pinfunction "2_2") (pintype "passive"))
      (node (ref "H8") (pin "1") (pinfunction "1_1") (pintype "passive"))
      (node (ref "T1") (pin "20") (pinfunction "VCC_20") (pintype "passive"))
      (node (ref "T2") (pin "20") (pinfunction "VCC_20") (pintype "passive"))
    )
    (net (code "95") (name "VIN") (class "Default")
      (node (ref "C2") (pin "2") (pinfunction "2_2") (pintype "passive"))
      (node (ref "D1") (pin "2") (pinfunction "2_2") (pintype "passive"))
      (node (ref "H2") (pin "2") (pinfunction "2_2") (pintype "passive"))
      (node (ref "IC1") (pin "2") (pinfunction "IN_2") (pintype "passive"))
      (node (ref "P1") (pin "1") (pinfunction "1_1") (pintype "passive"))
    )
    (net (code "96") (name "VIN-B") (class "Default")
      (node (ref "H2") (pin "1") (pinfunction "1_1") (pintype "passive"))
      (node (ref "H6") (pin "24") (pinfunction "8_24") (pintype "passive"))
    )
    (net (code "97") (name "unconnected-(H4-Pad8)") (class "Default")
      (node (ref "H4") (pin "8") (pinfunction "8_8") (pintype "passive"))
    )
    (net (code "98") (name "unconnected-(H6-1-Pad17)") (class "Default")
      (node (ref "H6") (pin "17") (pinfunction "1_17") (pintype "passive"))
    )
    (net (code "99") (name "unconnected-(J2-CDN-Pad9)") (class "Default")
      (node (ref "J2") (pin "9") (pinfunction "CDN_9") (pintype "passive"))
    )
    (net (code "100") (name "unconnected-(J2-DATA1-Pad8)") (class "Default")
      (node (ref "J2") (pin "8") (pinfunction "DATA1_8") (pintype "passive"))
    )
    (net (code "101") (name "unconnected-(J2-DATA2-Pad1)") (class "Default")
      (node (ref "J2") (pin "1") (pinfunction "DATA2_1") (pintype "passive"))
    )
  )
)
